# ESC_NoPilot.net
KiCad netlist of a schematic drawn in EAGLE
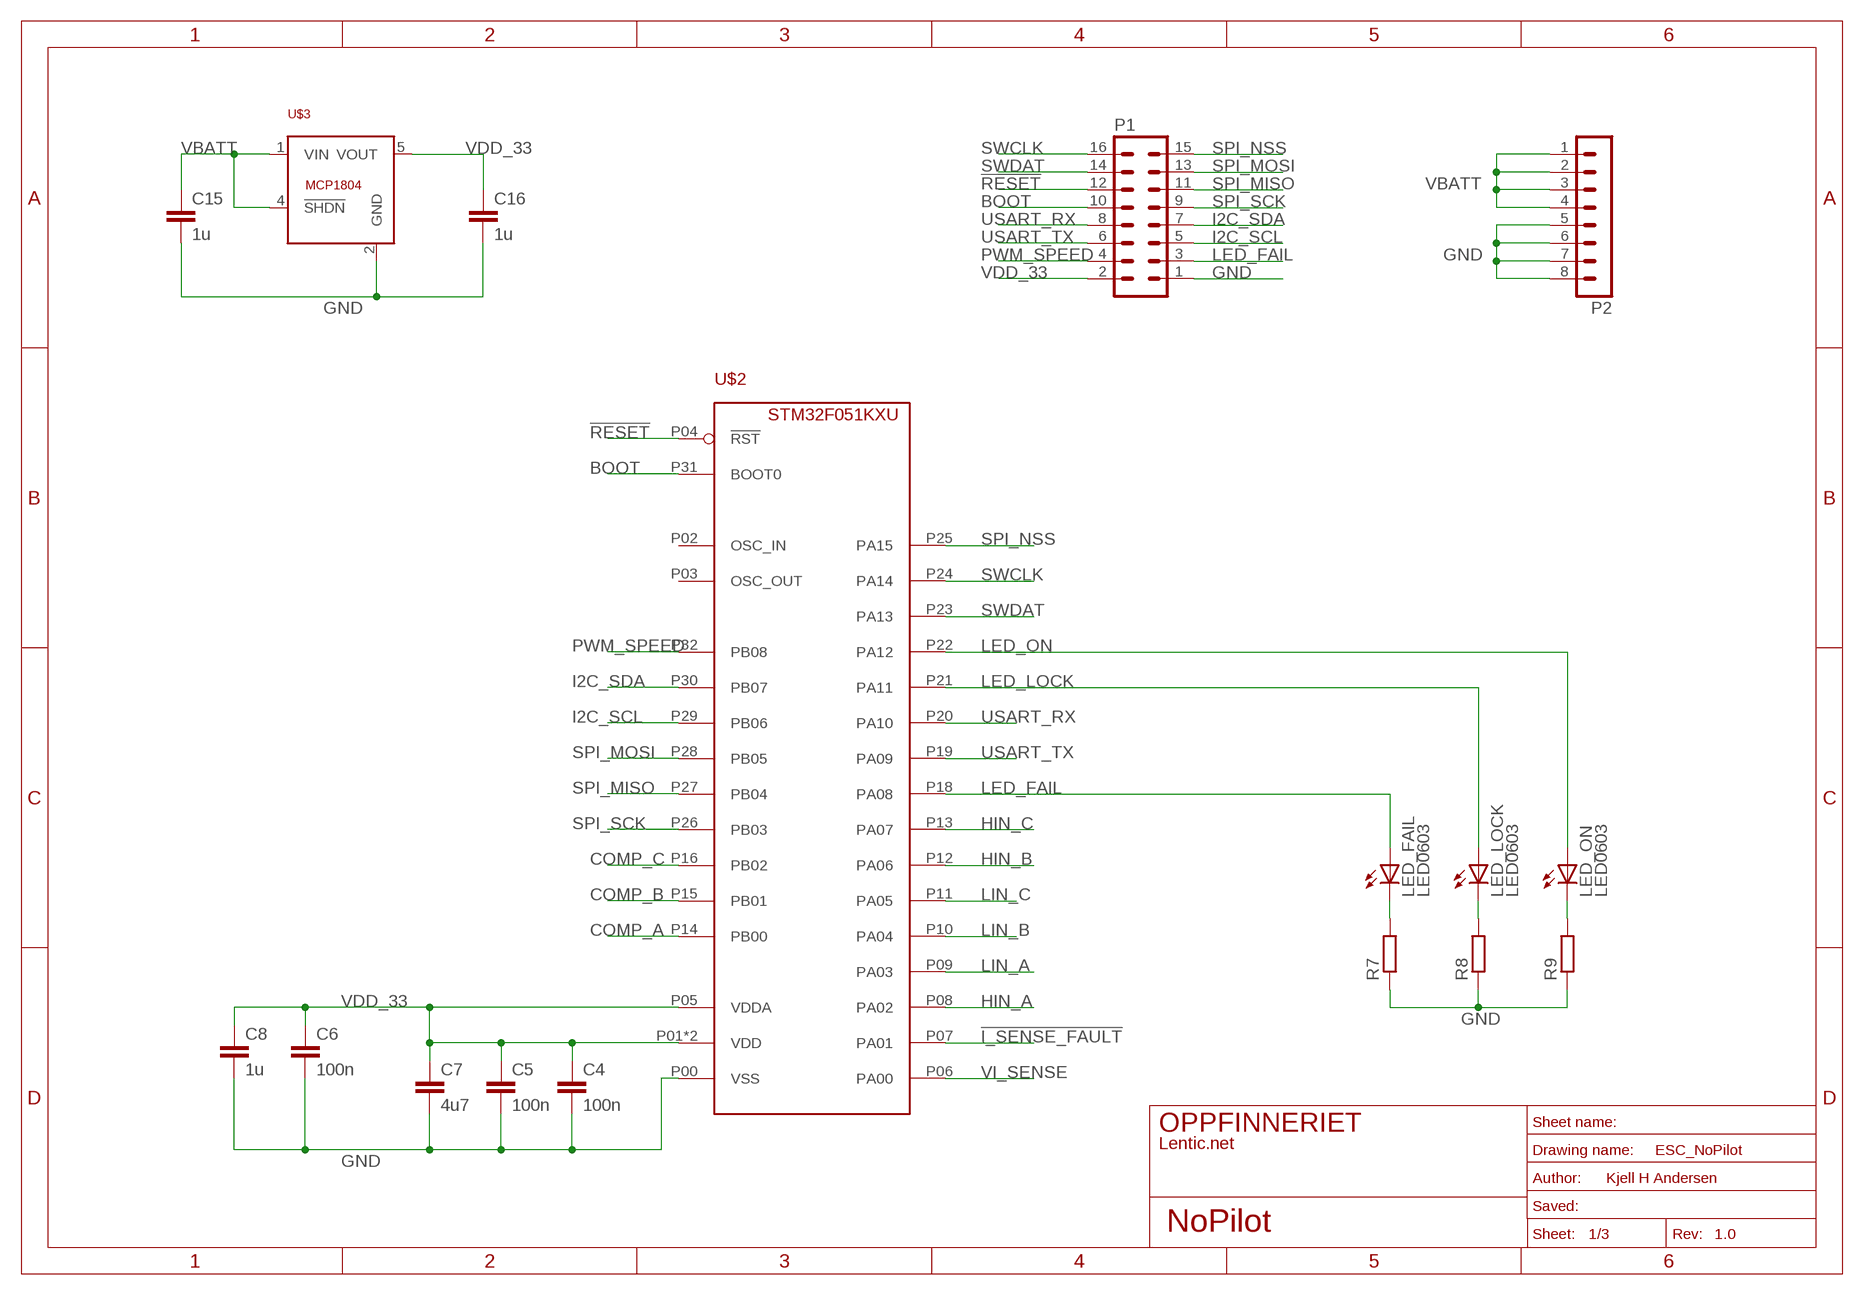
[diagram p0: schematic, sheet 1]
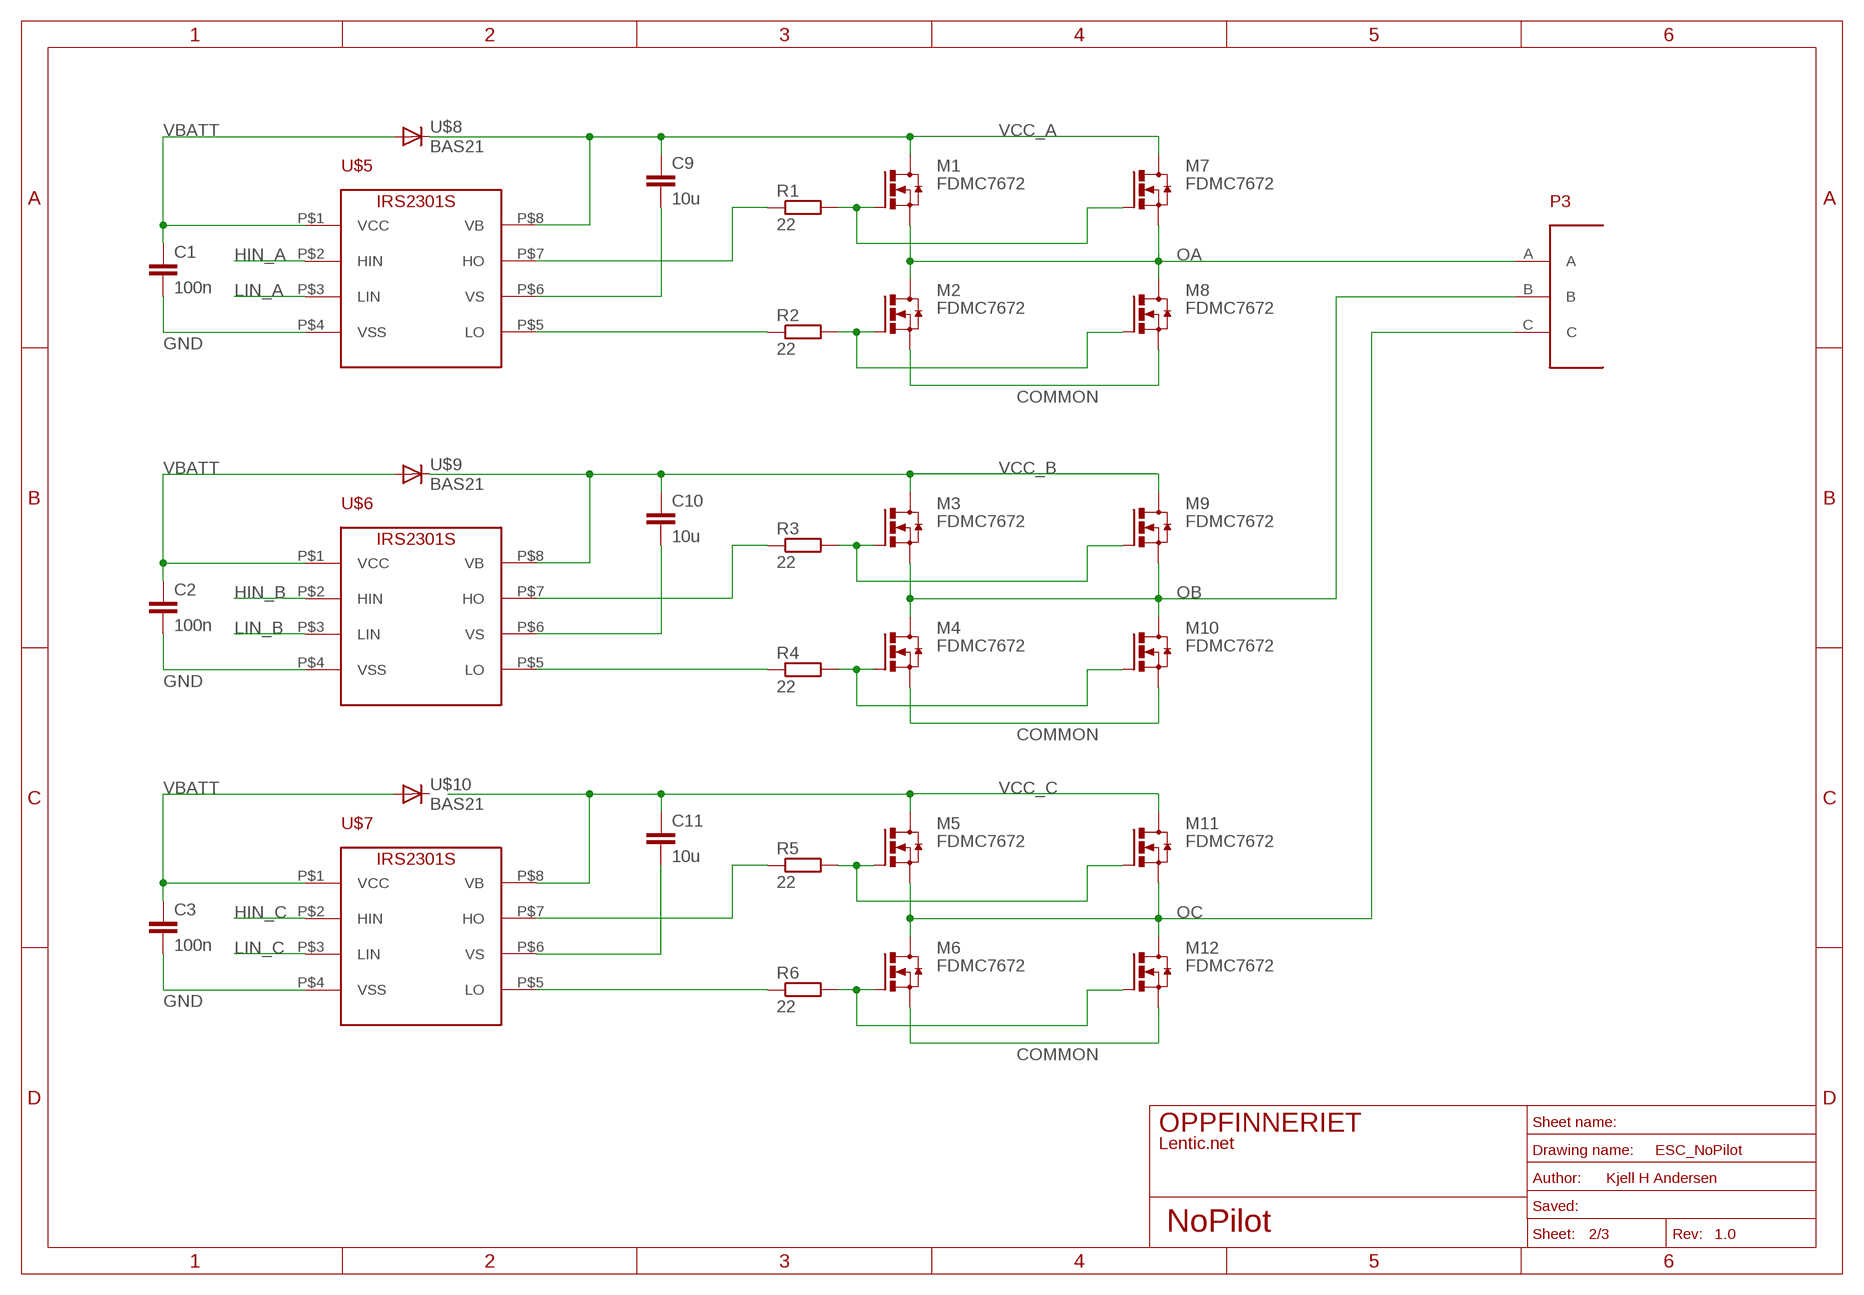
[diagram p1: schematic, sheet 2]
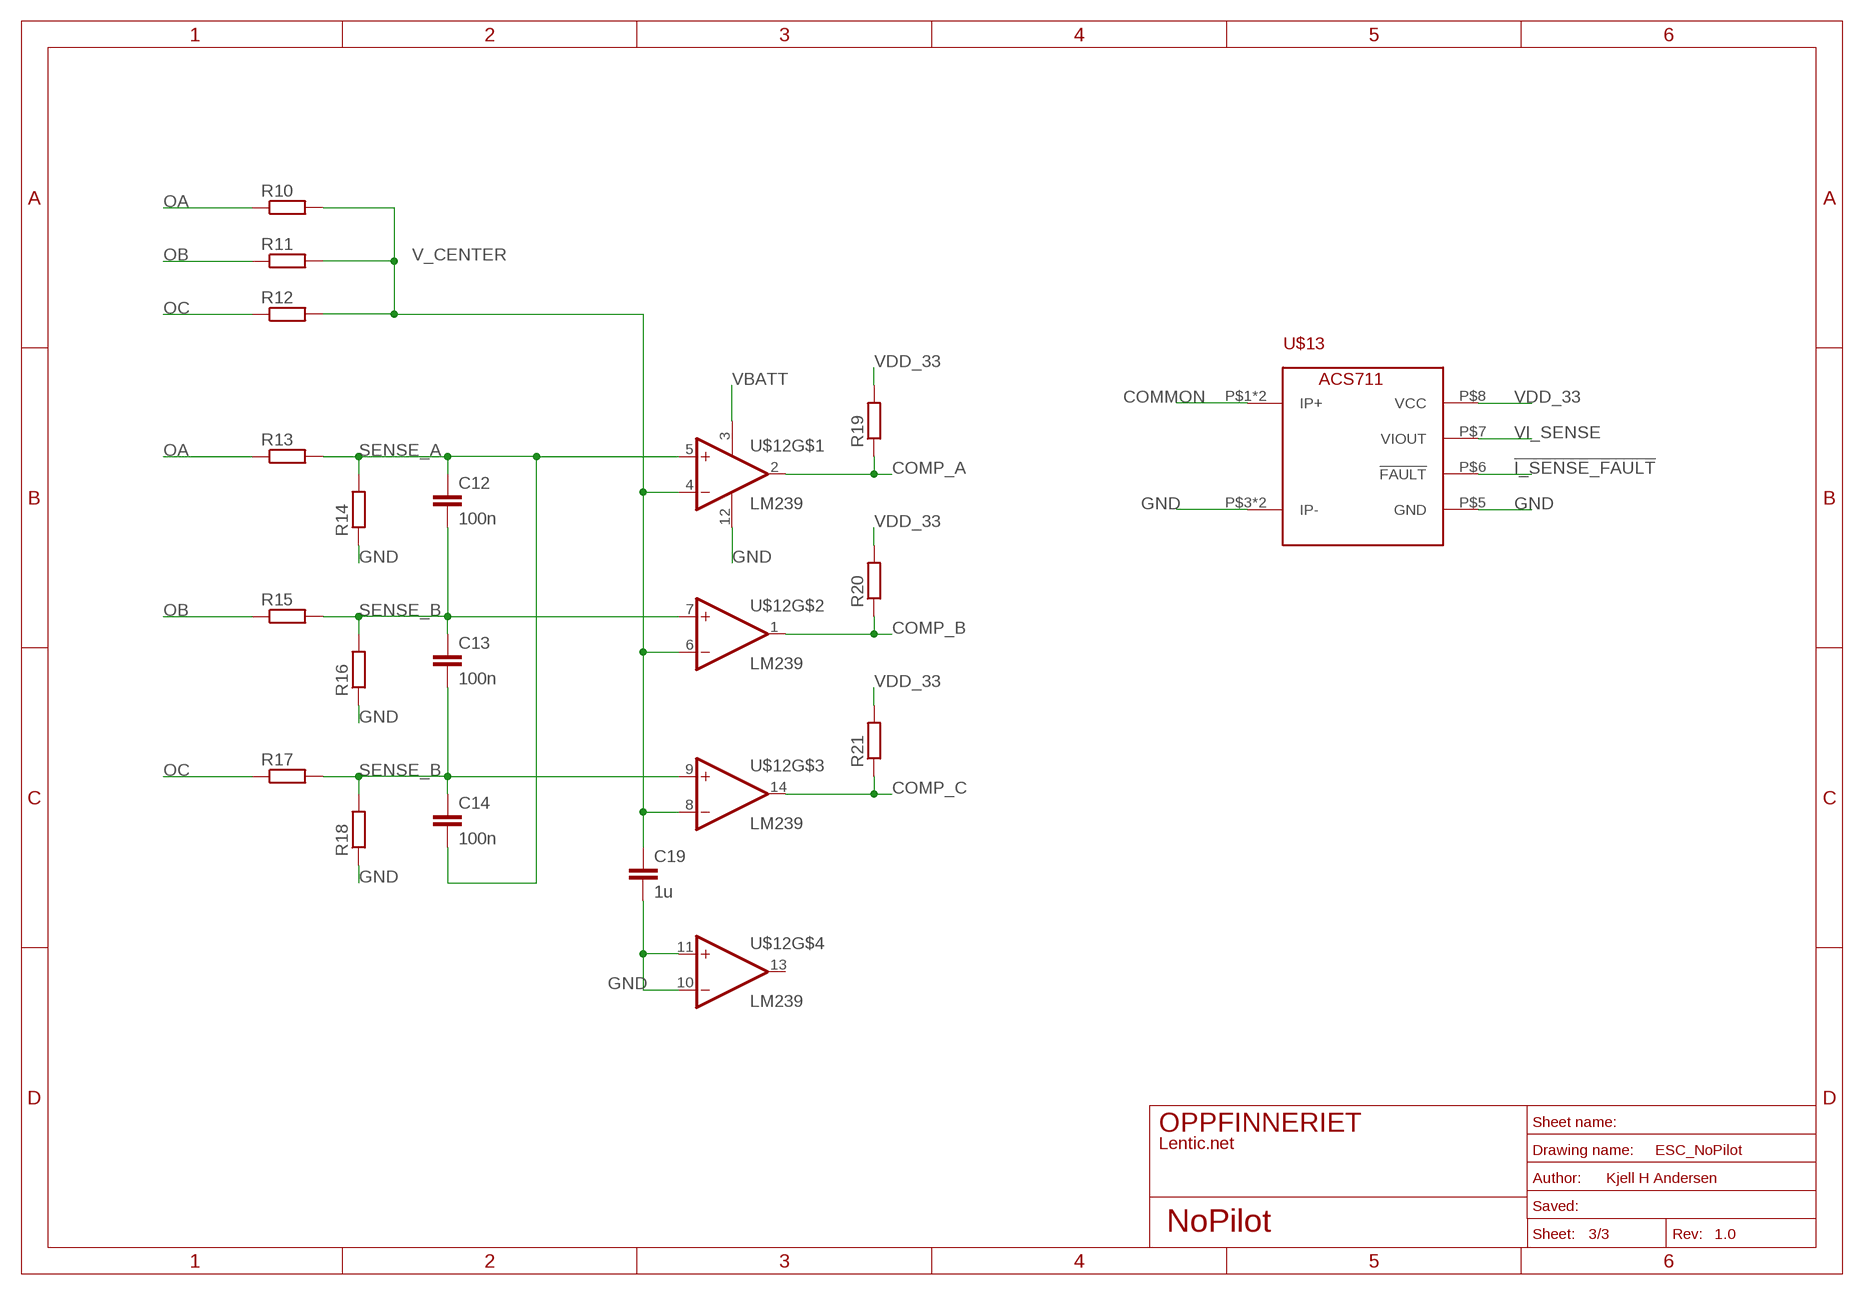
[diagram p2: schematic, sheet 3]

(export (version "E")
  (design (tool "Eeschema 10.0.6"))
  (components
    (comp (ref "C12")
      (value "100n")
      (footprint "eagle-import:C0402")
      (libsource (lib "eagle-import") (part "C-EUC0402"))
    )
    (comp (ref "C13")
      (value "100n")
      (footprint "eagle-import:C0402")
      (libsource (lib "eagle-import") (part "C-EUC0402"))
    )
    (comp (ref "C14")
      (value "100n")
      (footprint "eagle-import:C0402")
      (libsource (lib "eagle-import") (part "C-EUC0402"))
    )
    (comp (ref "C19")
      (value "1u")
      (footprint "eagle-import:C0805")
      (libsource (lib "eagle-import") (part "C-EUC0805"))
    )
    (comp (ref "R10")
      (value "R-EU_R0402")
      (footprint "eagle-import:R0402")
      (libsource (lib "eagle-import") (part "R-EU_R0402"))
    )
    (comp (ref "R11")
      (value "R-EU_R0402")
      (footprint "eagle-import:R0402")
      (libsource (lib "eagle-import") (part "R-EU_R0402"))
    )
    (comp (ref "R12")
      (value "R-EU_R0402")
      (footprint "eagle-import:R0402")
      (libsource (lib "eagle-import") (part "R-EU_R0402"))
    )
    (comp (ref "R13")
      (value "R-EU_R0402")
      (footprint "eagle-import:R0402")
      (libsource (lib "eagle-import") (part "R-EU_R0402"))
    )
    (comp (ref "R14")
      (value "R-EU_R0402")
      (footprint "eagle-import:R0402")
      (libsource (lib "eagle-import") (part "R-EU_R0402"))
    )
    (comp (ref "R15")
      (value "R-EU_R0402")
      (footprint "eagle-import:R0402")
      (libsource (lib "eagle-import") (part "R-EU_R0402"))
    )
    (comp (ref "R16")
      (value "R-EU_R0402")
      (footprint "eagle-import:R0402")
      (libsource (lib "eagle-import") (part "R-EU_R0402"))
    )
    (comp (ref "R17")
      (value "R-EU_R0402")
      (footprint "eagle-import:R0402")
      (libsource (lib "eagle-import") (part "R-EU_R0402"))
    )
    (comp (ref "R18")
      (value "R-EU_R0402")
      (footprint "eagle-import:R0402")
      (libsource (lib "eagle-import") (part "R-EU_R0402"))
    )
    (comp (ref "R19")
      (value "R-EU_R0402")
      (footprint "eagle-import:R0402")
      (libsource (lib "eagle-import") (part "R-EU_R0402"))
    )
    (comp (ref "R20")
      (value "R-EU_R0402")
      (footprint "eagle-import:R0402")
      (libsource (lib "eagle-import") (part "R-EU_R0402"))
    )
    (comp (ref "R21")
      (value "R-EU_R0402")
      (footprint "eagle-import:R0402")
      (libsource (lib "eagle-import") (part "R-EU_R0402"))
    )
    (comp (ref "U$12")
      (value "LM239")
      (footprint "eagle-import:TSSOP14")
      (libsource (lib "eagle-import") (part "LM239"))
    )
    (comp (ref "U$13")
      (value "ACS711")
      (footprint "eagle-import:SOIC8")
      (libsource (lib "eagle-import") (part "ACS711"))
    )
    (comp (ref "C4")
      (value "100n")
      (footprint "eagle-import:C0402")
      (libsource (lib "eagle-import") (part "C-EUC0402"))
    )
    (comp (ref "C5")
      (value "100n")
      (footprint "eagle-import:C0402")
      (libsource (lib "eagle-import") (part "C-EUC0402"))
    )
    (comp (ref "C6")
      (value "100n")
      (footprint "eagle-import:C0402")
      (libsource (lib "eagle-import") (part "C-EUC0402"))
    )
    (comp (ref "C7")
      (value "4u7")
      (footprint "eagle-import:C0805")
      (libsource (lib "eagle-import") (part "C-EUC0805"))
    )
    (comp (ref "C8")
      (value "1u")
      (footprint "eagle-import:C0805")
      (libsource (lib "eagle-import") (part "C-EUC0805"))
    )
    (comp (ref "C15")
      (value "1u")
      (footprint "eagle-import:C0805")
      (libsource (lib "eagle-import") (part "C-EUC0805"))
    )
    (comp (ref "C16")
      (value "1u")
      (footprint "eagle-import:C0805")
      (libsource (lib "eagle-import") (part "C-EUC0805"))
    )
    (comp (ref "LED_FAIL")
      (value "LED0603")
      (footprint "eagle-import:D0603")
      (libsource (lib "eagle-import") (part "LED0603"))
    )
    (comp (ref "LED_LOCK")
      (value "LED0603")
      (footprint "eagle-import:D0603")
      (libsource (lib "eagle-import") (part "LED0603"))
    )
    (comp (ref "LED_ON")
      (value "LED0603")
      (footprint "eagle-import:D0603")
      (libsource (lib "eagle-import") (part "LED0603"))
    )
    (comp (ref "P1")
      (value "MA08-2")
      (footprint "eagle-import:MA08-2")
      (libsource (lib "eagle-import") (part "MA08-2"))
    )
    (comp (ref "P2")
      (value "MA08-1")
      (footprint "eagle-import:MA08-1")
      (libsource (lib "eagle-import") (part "MA08-1"))
    )
    (comp (ref "R7")
      (value "R-EU_R0402")
      (footprint "eagle-import:R0402")
      (libsource (lib "eagle-import") (part "R-EU_R0402"))
    )
    (comp (ref "R8")
      (value "R-EU_R0402")
      (footprint "eagle-import:R0402")
      (libsource (lib "eagle-import") (part "R-EU_R0402"))
    )
    (comp (ref "R9")
      (value "R-EU_R0402")
      (footprint "eagle-import:R0402")
      (libsource (lib "eagle-import") (part "R-EU_R0402"))
    )
    (comp (ref "U$2")
      (value "STM32F051KXU")
      (footprint "eagle-import:UFQFPN32")
      (libsource (lib "eagle-import") (part "STM32F051KXU"))
    )
    (comp (ref "U$3")
      (value "MCP1804")
      (footprint "eagle-import:SOT23")
      (libsource (lib "eagle-import") (part "MCP1804"))
    )
    (comp (ref "C1")
      (value "100n")
      (footprint "eagle-import:C0402")
      (libsource (lib "eagle-import") (part "C-EUC0402"))
    )
    (comp (ref "C2")
      (value "100n")
      (footprint "eagle-import:C0402")
      (libsource (lib "eagle-import") (part "C-EUC0402"))
    )
    (comp (ref "C3")
      (value "100n")
      (footprint "eagle-import:C0402")
      (libsource (lib "eagle-import") (part "C-EUC0402"))
    )
    (comp (ref "C9")
      (value "10u")
      (footprint "eagle-import:C0805")
      (libsource (lib "eagle-import") (part "C-EUC0805"))
    )
    (comp (ref "C10")
      (value "10u")
      (footprint "eagle-import:C0805")
      (libsource (lib "eagle-import") (part "C-EUC0805"))
    )
    (comp (ref "C11")
      (value "10u")
      (footprint "eagle-import:C0805")
      (libsource (lib "eagle-import") (part "C-EUC0805"))
    )
    (comp (ref "M1")
      (value "FDMC7672")
      (footprint "eagle-import:MLP_3P3X3P3")
      (libsource (lib "eagle-import") (part "FDMC7672"))
    )
    (comp (ref "M2")
      (value "FDMC7672")
      (footprint "eagle-import:MLP_3P3X3P3")
      (libsource (lib "eagle-import") (part "FDMC7672"))
    )
    (comp (ref "M3")
      (value "FDMC7672")
      (footprint "eagle-import:MLP_3P3X3P3")
      (libsource (lib "eagle-import") (part "FDMC7672"))
    )
    (comp (ref "M4")
      (value "FDMC7672")
      (footprint "eagle-import:MLP_3P3X3P3")
      (libsource (lib "eagle-import") (part "FDMC7672"))
    )
    (comp (ref "M5")
      (value "FDMC7672")
      (footprint "eagle-import:MLP_3P3X3P3")
      (libsource (lib "eagle-import") (part "FDMC7672"))
    )
    (comp (ref "M6")
      (value "FDMC7672")
      (footprint "eagle-import:MLP_3P3X3P3")
      (libsource (lib "eagle-import") (part "FDMC7672"))
    )
    (comp (ref "M7")
      (value "FDMC7672")
      (footprint "eagle-import:MLP_3P3X3P3")
      (libsource (lib "eagle-import") (part "FDMC7672"))
    )
    (comp (ref "M8")
      (value "FDMC7672")
      (footprint "eagle-import:MLP_3P3X3P3")
      (libsource (lib "eagle-import") (part "FDMC7672"))
    )
    (comp (ref "M9")
      (value "FDMC7672")
      (footprint "eagle-import:MLP_3P3X3P3")
      (libsource (lib "eagle-import") (part "FDMC7672"))
    )
    (comp (ref "M10")
      (value "FDMC7672")
      (footprint "eagle-import:MLP_3P3X3P3")
      (libsource (lib "eagle-import") (part "FDMC7672"))
    )
    (comp (ref "M11")
      (value "FDMC7672")
      (footprint "eagle-import:MLP_3P3X3P3")
      (libsource (lib "eagle-import") (part "FDMC7672"))
    )
    (comp (ref "M12")
      (value "FDMC7672")
      (footprint "eagle-import:MLP_3P3X3P3")
      (libsource (lib "eagle-import") (part "FDMC7672"))
    )
    (comp (ref "P3")
      (value "3PH_SJ")
      (footprint "eagle-import:3PH_SJ")
      (libsource (lib "eagle-import") (part "3PH_SJ"))
    )
    (comp (ref "R1")
      (value "22")
      (footprint "eagle-import:R0402")
      (libsource (lib "eagle-import") (part "R-EU_R0402"))
    )
    (comp (ref "R2")
      (value "22")
      (footprint "eagle-import:R0402")
      (libsource (lib "eagle-import") (part "R-EU_R0402"))
    )
    (comp (ref "R3")
      (value "22")
      (footprint "eagle-import:R0402")
      (libsource (lib "eagle-import") (part "R-EU_R0402"))
    )
    (comp (ref "R4")
      (value "22")
      (footprint "eagle-import:R0402")
      (libsource (lib "eagle-import") (part "R-EU_R0402"))
    )
    (comp (ref "R5")
      (value "22")
      (footprint "eagle-import:R0402")
      (libsource (lib "eagle-import") (part "R-EU_R0402"))
    )
    (comp (ref "R6")
      (value "22")
      (footprint "eagle-import:R0402")
      (libsource (lib "eagle-import") (part "R-EU_R0402"))
    )
    (comp (ref "U$5")
      (value "IRS2301S")
      (footprint "eagle-import:SOIC8")
      (libsource (lib "eagle-import") (part "IRS2301S"))
    )
    (comp (ref "U$6")
      (value "IRS2301S")
      (footprint "eagle-import:SOIC8")
      (libsource (lib "eagle-import") (part "IRS2301S"))
    )
    (comp (ref "U$7")
      (value "IRS2301S")
      (footprint "eagle-import:SOIC8")
      (libsource (lib "eagle-import") (part "IRS2301S"))
    )
    (comp (ref "U$8")
      (value "BAS21")
      (footprint "eagle-import:SOT23-3")
      (libsource (lib "eagle-import") (part "BAS21"))
    )
    (comp (ref "U$9")
      (value "BAS21")
      (footprint "eagle-import:SOT23-3")
      (libsource (lib "eagle-import") (part "BAS21"))
    )
    (comp (ref "U$10")
      (value "BAS21")
      (footprint "eagle-import:SOT23-3")
      (libsource (lib "eagle-import") (part "BAS21"))
    )
  )
  (nets
    (net (code "1") (name "BOOT") (class "Default")
      (node (ref "P1") (pin "10") (pinfunction "10_10") (pintype "passive"))
      (node (ref "U$2") (pin "P31") (pinfunction "BOOT0_P31") (pintype "input"))
    )
    (net (code "2") (name "COMMON") (class "Default")
      (node (ref "M10") (pin "P1") (pinfunction "S_P1") (pintype "passive"))
      (node (ref "M10") (pin "P2") (pinfunction "S_P2") (pintype "passive"))
      (node (ref "M10") (pin "P3") (pinfunction "S_P3") (pintype "passive"))
      (node (ref "M12") (pin "P1") (pinfunction "S_P1") (pintype "passive"))
      (node (ref "M12") (pin "P2") (pinfunction "S_P2") (pintype "passive"))
      (node (ref "M12") (pin "P3") (pinfunction "S_P3") (pintype "passive"))
      (node (ref "M2") (pin "P1") (pinfunction "S_P1") (pintype "passive"))
      (node (ref "M2") (pin "P2") (pinfunction "S_P2") (pintype "passive"))
      (node (ref "M2") (pin "P3") (pinfunction "S_P3") (pintype "passive"))
      (node (ref "M4") (pin "P1") (pinfunction "S_P1") (pintype "passive"))
      (node (ref "M4") (pin "P2") (pinfunction "S_P2") (pintype "passive"))
      (node (ref "M4") (pin "P3") (pinfunction "S_P3") (pintype "passive"))
      (node (ref "M6") (pin "P1") (pinfunction "S_P1") (pintype "passive"))
      (node (ref "M6") (pin "P2") (pinfunction "S_P2") (pintype "passive"))
      (node (ref "M6") (pin "P3") (pinfunction "S_P3") (pintype "passive"))
      (node (ref "M8") (pin "P1") (pinfunction "S_P1") (pintype "passive"))
      (node (ref "M8") (pin "P2") (pinfunction "S_P2") (pintype "passive"))
      (node (ref "M8") (pin "P3") (pinfunction "S_P3") (pintype "passive"))
      (node (ref "U$13") (pin "P$1") (pinfunction "IP+_P$1") (pintype "bidirectional"))
      (node (ref "U$13") (pin "P$2") (pinfunction "IP+_P$2") (pintype "bidirectional"))
    )
    (net (code "3") (name "COMP_A") (class "Default")
      (node (ref "R19") (pin "1") (pinfunction "1_1") (pintype "passive"))
      (node (ref "U$12") (pin "2") (pinfunction "OUT_2") (pintype "open_collector"))
      (node (ref "U$2") (pin "P14") (pinfunction "PB00_P14") (pintype "bidirectional"))
    )
    (net (code "4") (name "COMP_B") (class "Default")
      (node (ref "R20") (pin "1") (pinfunction "1_1") (pintype "passive"))
      (node (ref "U$12") (pin "1") (pinfunction "OUT_1") (pintype "open_collector"))
      (node (ref "U$2") (pin "P15") (pinfunction "PB01_P15") (pintype "bidirectional"))
    )
    (net (code "5") (name "COMP_C") (class "Default")
      (node (ref "R21") (pin "1") (pinfunction "1_1") (pintype "passive"))
      (node (ref "U$12") (pin "14") (pinfunction "OUT_14") (pintype "open_collector"))
      (node (ref "U$2") (pin "P16") (pinfunction "PB02_P16") (pintype "bidirectional"))
    )
    (net (code "6") (name "GND") (class "Default")
      (node (ref "C1") (pin "2") (pinfunction "2_2") (pintype "passive"))
      (node (ref "C15") (pin "2") (pinfunction "2_2") (pintype "passive"))
      (node (ref "C16") (pin "2") (pinfunction "2_2") (pintype "passive"))
      (node (ref "C19") (pin "2") (pinfunction "2_2") (pintype "passive"))
      (node (ref "C2") (pin "2") (pinfunction "2_2") (pintype "passive"))
      (node (ref "C3") (pin "2") (pinfunction "2_2") (pintype "passive"))
      (node (ref "C4") (pin "2") (pinfunction "2_2") (pintype "passive"))
      (node (ref "C5") (pin "2") (pinfunction "2_2") (pintype "passive"))
      (node (ref "C6") (pin "2") (pinfunction "2_2") (pintype "passive"))
      (node (ref "C7") (pin "2") (pinfunction "2_2") (pintype "passive"))
      (node (ref "C8") (pin "2") (pinfunction "2_2") (pintype "passive"))
      (node (ref "P1") (pin "1") (pinfunction "1_1") (pintype "passive"))
      (node (ref "P2") (pin "5") (pinfunction "5_5") (pintype "passive"))
      (node (ref "P2") (pin "6") (pinfunction "6_6") (pintype "passive"))
      (node (ref "P2") (pin "7") (pinfunction "7_7") (pintype "passive"))
      (node (ref "P2") (pin "8") (pinfunction "8_8") (pintype "passive"))
      (node (ref "R14") (pin "1") (pinfunction "1_1") (pintype "passive"))
      (node (ref "R16") (pin "1") (pinfunction "1_1") (pintype "passive"))
      (node (ref "R18") (pin "1") (pinfunction "1_1") (pintype "passive"))
      (node (ref "R7") (pin "1") (pinfunction "1_1") (pintype "passive"))
      (node (ref "R8") (pin "1") (pinfunction "1_1") (pintype "passive"))
      (node (ref "R9") (pin "1") (pinfunction "1_1") (pintype "passive"))
      (node (ref "U$12") (pin "10") (pinfunction "-IN_10") (pintype "input"))
      (node (ref "U$12") (pin "11") (pinfunction "+IN_11") (pintype "input"))
      (node (ref "U$12") (pin "12") (pinfunction "GND_12") (pintype "power_in"))
      (node (ref "U$13") (pin "P$3") (pinfunction "IP-_P$3") (pintype "bidirectional"))
      (node (ref "U$13") (pin "P$4") (pinfunction "IP-_P$4") (pintype "bidirectional"))
      (node (ref "U$13") (pin "P$5") (pinfunction "GND_P$5") (pintype "bidirectional"))
      (node (ref "U$2") (pin "P00") (pinfunction "VSS_P00") (pintype "power_in"))
      (node (ref "U$3") (pin "2") (pinfunction "GND_2") (pintype "bidirectional"))
      (node (ref "U$5") (pin "P$4") (pinfunction "VSS_P$4") (pintype "bidirectional"))
      (node (ref "U$6") (pin "P$4") (pinfunction "VSS_P$4") (pintype "bidirectional"))
      (node (ref "U$7") (pin "P$4") (pinfunction "VSS_P$4") (pintype "bidirectional"))
    )
    (net (code "7") (name "HIN_A") (class "Default")
      (node (ref "U$2") (pin "P08") (pinfunction "PA02_P08") (pintype "bidirectional"))
      (node (ref "U$5") (pin "P$2") (pinfunction "HIN_P$2") (pintype "bidirectional"))
    )
    (net (code "8") (name "HIN_B") (class "Default")
      (node (ref "U$2") (pin "P12") (pinfunction "PA06_P12") (pintype "bidirectional"))
      (node (ref "U$6") (pin "P$2") (pinfunction "HIN_P$2") (pintype "bidirectional"))
    )
    (net (code "9") (name "HIN_C") (class "Default")
      (node (ref "U$2") (pin "P13") (pinfunction "PA07_P13") (pintype "bidirectional"))
      (node (ref "U$7") (pin "P$2") (pinfunction "HIN_P$2") (pintype "bidirectional"))
    )
    (net (code "10") (name "I2C_SCL") (class "Default")
      (node (ref "P1") (pin "5") (pinfunction "5_5") (pintype "passive"))
      (node (ref "U$2") (pin "P29") (pinfunction "PB06_P29") (pintype "bidirectional"))
    )
    (net (code "11") (name "I2C_SDA") (class "Default")
      (node (ref "P1") (pin "7") (pinfunction "7_7") (pintype "passive"))
      (node (ref "U$2") (pin "P30") (pinfunction "PB07_P30") (pintype "bidirectional"))
    )
    (net (code "12") (name "LED_FAIL") (class "Default")
      (node (ref "LED_FAIL") (pin "A") (pinfunction "A_A") (pintype "passive"))
      (node (ref "P1") (pin "3") (pinfunction "3_3") (pintype "passive"))
      (node (ref "U$2") (pin "P18") (pinfunction "PA08_P18") (pintype "bidirectional"))
    )
    (net (code "13") (name "LED_LOCK") (class "Default")
      (node (ref "LED_LOCK") (pin "A") (pinfunction "A_A") (pintype "passive"))
      (node (ref "U$2") (pin "P21") (pinfunction "PA11_P21") (pintype "bidirectional"))
    )
    (net (code "14") (name "LED_ON") (class "Default")
      (node (ref "LED_ON") (pin "A") (pinfunction "A_A") (pintype "passive"))
      (node (ref "U$2") (pin "P22") (pinfunction "PA12_P22") (pintype "bidirectional"))
    )
    (net (code "15") (name "LIN_A") (class "Default")
      (node (ref "U$2") (pin "P09") (pinfunction "PA03_P09") (pintype "bidirectional"))
      (node (ref "U$5") (pin "P$3") (pinfunction "LIN_P$3") (pintype "bidirectional"))
    )
    (net (code "16") (name "LIN_B") (class "Default")
      (node (ref "U$2") (pin "P10") (pinfunction "PA04_P10") (pintype "bidirectional"))
      (node (ref "U$6") (pin "P$3") (pinfunction "LIN_P$3") (pintype "bidirectional"))
    )
    (net (code "17") (name "LIN_C") (class "Default")
      (node (ref "U$2") (pin "P11") (pinfunction "PA05_P11") (pintype "bidirectional"))
      (node (ref "U$7") (pin "P$3") (pinfunction "LIN_P$3") (pintype "bidirectional"))
    )
    (net (code "18") (name "Net-(LED_FAIL-PadC)") (class "Default")
      (node (ref "LED_FAIL") (pin "C") (pinfunction "C_C") (pintype "passive"))
      (node (ref "R7") (pin "2") (pinfunction "2_2") (pintype "passive"))
    )
    (net (code "19") (name "Net-(LED_LOCK-PadC)") (class "Default")
      (node (ref "LED_LOCK") (pin "C") (pinfunction "C_C") (pintype "passive"))
      (node (ref "R8") (pin "2") (pinfunction "2_2") (pintype "passive"))
    )
    (net (code "20") (name "Net-(LED_ON-PadC)") (class "Default")
      (node (ref "LED_ON") (pin "C") (pinfunction "C_C") (pintype "passive"))
      (node (ref "R9") (pin "2") (pinfunction "2_2") (pintype "passive"))
    )
    (net (code "21") (name "Net-(M1-G)") (class "Default")
      (node (ref "M1") (pin "P4") (pinfunction "G_P4") (pintype "passive"))
      (node (ref "M7") (pin "P4") (pinfunction "G_P4") (pintype "passive"))
      (node (ref "R1") (pin "2") (pinfunction "2_2") (pintype "passive"))
    )
    (net (code "22") (name "Net-(M2-G)") (class "Default")
      (node (ref "M2") (pin "P4") (pinfunction "G_P4") (pintype "passive"))
      (node (ref "M8") (pin "P4") (pinfunction "G_P4") (pintype "passive"))
      (node (ref "R2") (pin "2") (pinfunction "2_2") (pintype "passive"))
    )
    (net (code "23") (name "Net-(M3-G)") (class "Default")
      (node (ref "M3") (pin "P4") (pinfunction "G_P4") (pintype "passive"))
      (node (ref "M9") (pin "P4") (pinfunction "G_P4") (pintype "passive"))
      (node (ref "R3") (pin "2") (pinfunction "2_2") (pintype "passive"))
    )
    (net (code "24") (name "Net-(M10-G)") (class "Default")
      (node (ref "M10") (pin "P4") (pinfunction "G_P4") (pintype "passive"))
      (node (ref "M4") (pin "P4") (pinfunction "G_P4") (pintype "passive"))
      (node (ref "R4") (pin "2") (pinfunction "2_2") (pintype "passive"))
    )
    (net (code "25") (name "Net-(M11-G)") (class "Default")
      (node (ref "M11") (pin "P4") (pinfunction "G_P4") (pintype "passive"))
      (node (ref "M5") (pin "P4") (pinfunction "G_P4") (pintype "passive"))
      (node (ref "R5") (pin "2") (pinfunction "2_2") (pintype "passive"))
    )
    (net (code "26") (name "Net-(M12-G)") (class "Default")
      (node (ref "M12") (pin "P4") (pinfunction "G_P4") (pintype "passive"))
      (node (ref "M6") (pin "P4") (pinfunction "G_P4") (pintype "passive"))
      (node (ref "R6") (pin "2") (pinfunction "2_2") (pintype "passive"))
    )
    (net (code "27") (name "Net-(U$5-HO)") (class "Default")
      (node (ref "R1") (pin "1") (pinfunction "1_1") (pintype "passive"))
      (node (ref "U$5") (pin "P$7") (pinfunction "HO_P$7") (pintype "bidirectional"))
    )
    (net (code "28") (name "Net-(U$5-LO)") (class "Default")
      (node (ref "R2") (pin "1") (pinfunction "1_1") (pintype "passive"))
      (node (ref "U$5") (pin "P$5") (pinfunction "LO_P$5") (pintype "bidirectional"))
    )
    (net (code "29") (name "Net-(U$5-VS)") (class "Default")
      (node (ref "C9") (pin "2") (pinfunction "2_2") (pintype "passive"))
      (node (ref "U$5") (pin "P$6") (pinfunction "VS_P$6") (pintype "bidirectional"))
    )
    (net (code "30") (name "Net-(U$6-HO)") (class "Default")
      (node (ref "R3") (pin "1") (pinfunction "1_1") (pintype "passive"))
      (node (ref "U$6") (pin "P$7") (pinfunction "HO_P$7") (pintype "bidirectional"))
    )
    (net (code "31") (name "Net-(U$6-LO)") (class "Default")
      (node (ref "R4") (pin "1") (pinfunction "1_1") (pintype "passive"))
      (node (ref "U$6") (pin "P$5") (pinfunction "LO_P$5") (pintype "bidirectional"))
    )
    (net (code "32") (name "Net-(U$6-VS)") (class "Default")
      (node (ref "C10") (pin "2") (pinfunction "2_2") (pintype "passive"))
      (node (ref "U$6") (pin "P$6") (pinfunction "VS_P$6") (pintype "bidirectional"))
    )
    (net (code "33") (name "Net-(U$7-HO)") (class "Default")
      (node (ref "R5") (pin "1") (pinfunction "1_1") (pintype "passive"))
      (node (ref "U$7") (pin "P$7") (pinfunction "HO_P$7") (pintype "bidirectional"))
    )
    (net (code "34") (name "Net-(U$7-LO)") (class "Default")
      (node (ref "R6") (pin "1") (pinfunction "1_1") (pintype "passive"))
      (node (ref "U$7") (pin "P$5") (pinfunction "LO_P$5") (pintype "bidirectional"))
    )
    (net (code "35") (name "Net-(U$7-VS)") (class "Default")
      (node (ref "C11") (pin "2") (pinfunction "2_2") (pintype "passive"))
      (node (ref "U$7") (pin "P$6") (pinfunction "VS_P$6") (pintype "bidirectional"))
    )
    (net (code "36") (name "OA") (class "Default")
      (node (ref "M1") (pin "P1") (pinfunction "S_P1") (pintype "passive"))
      (node (ref "M1") (pin "P2") (pinfunction "S_P2") (pintype "passive"))
      (node (ref "M1") (pin "P3") (pinfunction "S_P3") (pintype "passive"))
      (node (ref "M2") (pin "P0") (pinfunction "D_P0") (pintype "passive"))
      (node (ref "M2") (pin "P5") (pinfunction "D_P5") (pintype "passive"))
      (node (ref "M2") (pin "P6") (pinfunction "D_P6") (pintype "passive"))
      (node (ref "M2") (pin "P7") (pinfunction "D_P7") (pintype "passive"))
      (node (ref "M2") (pin "P8") (pinfunction "D_P8") (pintype "passive"))
      (node (ref "M7") (pin "P1") (pinfunction "S_P1") (pintype "passive"))
      (node (ref "M7") (pin "P2") (pinfunction "S_P2") (pintype "passive"))
      (node (ref "M7") (pin "P3") (pinfunction "S_P3") (pintype "passive"))
      (node (ref "M8") (pin "P0") (pinfunction "D_P0") (pintype "passive"))
      (node (ref "M8") (pin "P5") (pinfunction "D_P5") (pintype "passive"))
      (node (ref "M8") (pin "P6") (pinfunction "D_P6") (pintype "passive"))
      (node (ref "M8") (pin "P7") (pinfunction "D_P7") (pintype "passive"))
      (node (ref "M8") (pin "P8") (pinfunction "D_P8") (pintype "passive"))
      (node (ref "P3") (pin "A") (pinfunction "A_A") (pintype "bidirectional"))
      (node (ref "R10") (pin "1") (pinfunction "1_1") (pintype "passive"))
      (node (ref "R13") (pin "1") (pinfunction "1_1") (pintype "passive"))
    )
    (net (code "37") (name "OB") (class "Default")
      (node (ref "M10") (pin "P0") (pinfunction "D_P0") (pintype "passive"))
      (node (ref "M10") (pin "P5") (pinfunction "D_P5") (pintype "passive"))
      (node (ref "M10") (pin "P6") (pinfunction "D_P6") (pintype "passive"))
      (node (ref "M10") (pin "P7") (pinfunction "D_P7") (pintype "passive"))
      (node (ref "M10") (pin "P8") (pinfunction "D_P8") (pintype "passive"))
      (node (ref "M3") (pin "P1") (pinfunction "S_P1") (pintype "passive"))
      (node (ref "M3") (pin "P2") (pinfunction "S_P2") (pintype "passive"))
      (node (ref "M3") (pin "P3") (pinfunction "S_P3") (pintype "passive"))
      (node (ref "M4") (pin "P0") (pinfunction "D_P0") (pintype "passive"))
      (node (ref "M4") (pin "P5") (pinfunction "D_P5") (pintype "passive"))
      (node (ref "M4") (pin "P6") (pinfunction "D_P6") (pintype "passive"))
      (node (ref "M4") (pin "P7") (pinfunction "D_P7") (pintype "passive"))
      (node (ref "M4") (pin "P8") (pinfunction "D_P8") (pintype "passive"))
      (node (ref "M9") (pin "P1") (pinfunction "S_P1") (pintype "passive"))
      (node (ref "M9") (pin "P2") (pinfunction "S_P2") (pintype "passive"))
      (node (ref "M9") (pin "P3") (pinfunction "S_P3") (pintype "passive"))
      (node (ref "P3") (pin "B") (pinfunction "B_B") (pintype "bidirectional"))
      (node (ref "R11") (pin "1") (pinfunction "1_1") (pintype "passive"))
      (node (ref "R15") (pin "1") (pinfunction "1_1") (pintype "passive"))
    )
    (net (code "38") (name "OC") (class "Default")
      (node (ref "M11") (pin "P1") (pinfunction "S_P1") (pintype "passive"))
      (node (ref "M11") (pin "P2") (pinfunction "S_P2") (pintype "passive"))
      (node (ref "M11") (pin "P3") (pinfunction "S_P3") (pintype "passive"))
      (node (ref "M12") (pin "P0") (pinfunction "D_P0") (pintype "passive"))
      (node (ref "M12") (pin "P5") (pinfunction "D_P5") (pintype "passive"))
      (node (ref "M12") (pin "P6") (pinfunction "D_P6") (pintype "passive"))
      (node (ref "M12") (pin "P7") (pinfunction "D_P7") (pintype "passive"))
      (node (ref "M12") (pin "P8") (pinfunction "D_P8") (pintype "passive"))
      (node (ref "M5") (pin "P1") (pinfunction "S_P1") (pintype "passive"))
      (node (ref "M5") (pin "P2") (pinfunction "S_P2") (pintype "passive"))
      (node (ref "M5") (pin "P3") (pinfunction "S_P3") (pintype "passive"))
      (node (ref "M6") (pin "P0") (pinfunction "D_P0") (pintype "passive"))
      (node (ref "M6") (pin "P5") (pinfunction "D_P5") (pintype "passive"))
      (node (ref "M6") (pin "P6") (pinfunction "D_P6") (pintype "passive"))
      (node (ref "M6") (pin "P7") (pinfunction "D_P7") (pintype "passive"))
      (node (ref "M6") (pin "P8") (pinfunction "D_P8") (pintype "passive"))
      (node (ref "P3") (pin "C") (pinfunction "C_C") (pintype "bidirectional"))
      (node (ref "R12") (pin "1") (pinfunction "1_1") (pintype "passive"))
      (node (ref "R17") (pin "1") (pinfunction "1_1") (pintype "passive"))
    )
    (net (code "39") (name "PWM_SPEED") (class "Default")
      (node (ref "P1") (pin "4") (pinfunction "4_4") (pintype "passive"))
      (node (ref "U$2") (pin "P32") (pinfunction "PB08_P32") (pintype "bidirectional"))
    )
    (net (code "40") (name "SENSE_A") (class "Default")
      (node (ref "C12") (pin "1") (pinfunction "1_1") (pintype "passive"))
      (node (ref "C14") (pin "2") (pinfunction "2_2") (pintype "passive"))
      (node (ref "R13") (pin "2") (pinfunction "2_2") (pintype "passive"))
      (node (ref "R14") (pin "2") (pinfunction "2_2") (pintype "passive"))
      (node (ref "U$12") (pin "5") (pinfunction "+IN_5") (pintype "input"))
    )
    (net (code "41") (name "SENSE_B") (class "Default")
      (node (ref "C12") (pin "2") (pinfunction "2_2") (pintype "passive"))
      (node (ref "C13") (pin "1") (pinfunction "1_1") (pintype "passive"))
      (node (ref "C13") (pin "2") (pinfunction "2_2") (pintype "passive"))
      (node (ref "C14") (pin "1") (pinfunction "1_1") (pintype "passive"))
      (node (ref "R15") (pin "2") (pinfunction "2_2") (pintype "passive"))
      (node (ref "R16") (pin "2") (pinfunction "2_2") (pintype "passive"))
      (node (ref "R17") (pin "2") (pinfunction "2_2") (pintype "passive"))
      (node (ref "R18") (pin "2") (pinfunction "2_2") (pintype "passive"))
      (node (ref "U$12") (pin "7") (pinfunction "+IN_7") (pintype "input"))
      (node (ref "U$12") (pin "9") (pinfunction "+IN_9") (pintype "input"))
    )
    (net (code "42") (name "SPI_MISO") (class "Default")
      (node (ref "P1") (pin "11") (pinfunction "11_11") (pintype "passive"))
      (node (ref "U$2") (pin "P27") (pinfunction "PB04_P27") (pintype "bidirectional"))
    )
    (net (code "43") (name "SPI_MOSI") (class "Default")
      (node (ref "P1") (pin "13") (pinfunction "13_13") (pintype "passive"))
      (node (ref "U$2") (pin "P28") (pinfunction "PB05_P28") (pintype "bidirectional"))
    )
    (net (code "44") (name "SPI_NSS") (class "Default")
      (node (ref "P1") (pin "15") (pinfunction "15_15") (pintype "passive"))
      (node (ref "U$2") (pin "P25") (pinfunction "PA15_P25") (pintype "bidirectional"))
    )
    (net (code "45") (name "SPI_SCK") (class "Default")
      (node (ref "P1") (pin "9") (pinfunction "9_9") (pintype "passive"))
      (node (ref "U$2") (pin "P26") (pinfunction "PB03_P26") (pintype "bidirectional"))
    )
    (net (code "46") (name "SWCLK") (class "Default")
      (node (ref "P1") (pin "16") (pinfunction "16_16") (pintype "passive"))
      (node (ref "U$2") (pin "P24") (pinfunction "PA14_P24") (pintype "bidirectional"))
    )
    (net (code "47") (name "SWDAT") (class "Default")
      (node (ref "P1") (pin "14") (pinfunction "14_14") (pintype "passive"))
      (node (ref "U$2") (pin "P23") (pinfunction "PA13_P23") (pintype "bidirectional"))
    )
    (net (code "48") (name "USART_RX") (class "Default")
      (node (ref "P1") (pin "8") (pinfunction "8_8") (pintype "passive"))
      (node (ref "U$2") (pin "P20") (pinfunction "PA10_P20") (pintype "bidirectional"))
    )
    (net (code "49") (name "USART_TX") (class "Default")
      (node (ref "P1") (pin "6") (pinfunction "6_6") (pintype "passive"))
      (node (ref "U$2") (pin "P19") (pinfunction "PA09_P19") (pintype "bidirectional"))
    )
    (net (code "50") (name "VBATT") (class "Default")
      (node (ref "C1") (pin "1") (pinfunction "1_1") (pintype "passive"))
      (node (ref "C15") (pin "1") (pinfunction "1_1") (pintype "passive"))
      (node (ref "C2") (pin "1") (pinfunction "1_1") (pintype "passive"))
      (node (ref "C3") (pin "1") (pinfunction "1_1") (pintype "passive"))
      (node (ref "P2") (pin "1") (pinfunction "1_1") (pintype "passive"))
      (node (ref "P2") (pin "2") (pinfunction "2_2") (pintype "passive"))
      (node (ref "P2") (pin "3") (pinfunction "3_3") (pintype "passive"))
      (node (ref "P2") (pin "4") (pinfunction "4_4") (pintype "passive"))
      (node (ref "U$10") (pin "P1") (pinfunction "A_P1") (pintype "passive"))
      (node (ref "U$12") (pin "3") (pinfunction "V+_3") (pintype "power_in"))
      (node (ref "U$3") (pin "1") (pinfunction "VIN_1") (pintype "bidirectional"))
      (node (ref "U$3") (pin "4") (pinfunction "~{SHDN}_4") (pintype "bidirectional"))
      (node (ref "U$5") (pin "P$1") (pinfunction "VCC_P$1") (pintype "bidirectional"))
      (node (ref "U$6") (pin "P$1") (pinfunction "VCC_P$1") (pintype "bidirectional"))
      (node (ref "U$7") (pin "P$1") (pinfunction "VCC_P$1") (pintype "bidirectional"))
      (node (ref "U$8") (pin "P1") (pinfunction "A_P1") (pintype "passive"))
      (node (ref "U$9") (pin "P1") (pinfunction "A_P1") (pintype "passive"))
    )
    (net (code "51") (name "VCC_A") (class "Default")
      (node (ref "C9") (pin "1") (pinfunction "1_1") (pintype "passive"))
      (node (ref "M1") (pin "P0") (pinfunction "D_P0") (pintype "passive"))
      (node (ref "M1") (pin "P5") (pinfunction "D_P5") (pintype "passive"))
      (node (ref "M1") (pin "P6") (pinfunction "D_P6") (pintype "passive"))
      (node (ref "M1") (pin "P7") (pinfunction "D_P7") (pintype "passive"))
      (node (ref "M1") (pin "P8") (pinfunction "D_P8") (pintype "passive"))
      (node (ref "M7") (pin "P0") (pinfunction "D_P0") (pintype "passive"))
      (node (ref "M7") (pin "P5") (pinfunction "D_P5") (pintype "passive"))
      (node (ref "M7") (pin "P6") (pinfunction "D_P6") (pintype "passive"))
      (node (ref "M7") (pin "P7") (pinfunction "D_P7") (pintype "passive"))
      (node (ref "M7") (pin "P8") (pinfunction "D_P8") (pintype "passive"))
      (node (ref "U$5") (pin "P$8") (pinfunction "VB_P$8") (pintype "bidirectional"))
      (node (ref "U$8") (pin "P3") (pinfunction "C_P3") (pintype "passive"))
    )
    (net (code "52") (name "VCC_B") (class "Default")
      (node (ref "C10") (pin "1") (pinfunction "1_1") (pintype "passive"))
      (node (ref "M3") (pin "P0") (pinfunction "D_P0") (pintype "passive"))
      (node (ref "M3") (pin "P5") (pinfunction "D_P5") (pintype "passive"))
      (node (ref "M3") (pin "P6") (pinfunction "D_P6") (pintype "passive"))
      (node (ref "M3") (pin "P7") (pinfunction "D_P7") (pintype "passive"))
      (node (ref "M3") (pin "P8") (pinfunction "D_P8") (pintype "passive"))
      (node (ref "M9") (pin "P0") (pinfunction "D_P0") (pintype "passive"))
      (node (ref "M9") (pin "P5") (pinfunction "D_P5") (pintype "passive"))
      (node (ref "M9") (pin "P6") (pinfunction "D_P6") (pintype "passive"))
      (node (ref "M9") (pin "P7") (pinfunction "D_P7") (pintype "passive"))
      (node (ref "M9") (pin "P8") (pinfunction "D_P8") (pintype "passive"))
      (node (ref "U$6") (pin "P$8") (pinfunction "VB_P$8") (pintype "bidirectional"))
      (node (ref "U$9") (pin "P3") (pinfunction "C_P3") (pintype "passive"))
    )
    (net (code "53") (name "VCC_C") (class "Default")
      (node (ref "C11") (pin "1") (pinfunction "1_1") (pintype "passive"))
      (node (ref "M11") (pin "P0") (pinfunction "D_P0") (pintype "passive"))
      (node (ref "M11") (pin "P5") (pinfunction "D_P5") (pintype "passive"))
      (node (ref "M11") (pin "P6") (pinfunction "D_P6") (pintype "passive"))
      (node (ref "M11") (pin "P7") (pinfunction "D_P7") (pintype "passive"))
      (node (ref "M11") (pin "P8") (pinfunction "D_P8") (pintype "passive"))
      (node (ref "M5") (pin "P0") (pinfunction "D_P0") (pintype "passive"))
      (node (ref "M5") (pin "P5") (pinfunction "D_P5") (pintype "passive"))
      (node (ref "M5") (pin "P6") (pinfunction "D_P6") (pintype "passive"))
      (node (ref "M5") (pin "P7") (pinfunction "D_P7") (pintype "passive"))
      (node (ref "M5") (pin "P8") (pinfunction "D_P8") (pintype "passive"))
      (node (ref "U$7") (pin "P$8") (pinfunction "VB_P$8") (pintype "bidirectional"))
    )
    (net (code "54") (name "VDD_33") (class "Default")
      (node (ref "C16") (pin "1") (pinfunction "1_1") (pintype "passive"))
      (node (ref "C4") (pin "1") (pinfunction "1_1") (pintype "passive"))
      (node (ref "C5") (pin "1") (pinfunction "1_1") (pintype "passive"))
      (node (ref "C6") (pin "1") (pinfunction "1_1") (pintype "passive"))
      (node (ref "C7") (pin "1") (pinfunction "1_1") (pintype "passive"))
      (node (ref "C8") (pin "1") (pinfunction "1_1") (pintype "passive"))
      (node (ref "P1") (pin "2") (pinfunction "2_2") (pintype "passive"))
      (node (ref "R19") (pin "2") (pinfunction "2_2") (pintype "passive"))
      (node (ref "R20") (pin "2") (pinfunction "2_2") (pintype "passive"))
      (node (ref "R21") (pin "2") (pinfunction "2_2") (pintype "passive"))
      (node (ref "U$13") (pin "P$8") (pinfunction "VCC_P$8") (pintype "bidirectional"))
      (node (ref "U$2") (pin "P01") (pinfunction "VDD_P01") (pintype "power_in"))
      (node (ref "U$2") (pin "P05") (pinfunction "VDDA_P05") (pintype "power_in"))
      (node (ref "U$2") (pin "P17") (pinfunction "VDD_P17") (pintype "power_in"))
      (node (ref "U$3") (pin "5") (pinfunction "VOUT_5") (pintype "bidirectional"))
    )
    (net (code "55") (name "VI_SENSE") (class "Default")
      (node (ref "U$13") (pin "P$7") (pinfunction "VIOUT_P$7") (pintype "bidirectional"))
      (node (ref "U$2") (pin "P06") (pinfunction "PA00_P06") (pintype "bidirectional"))
    )
    (net (code "56") (name "V_CENTER") (class "Default")
      (node (ref "C19") (pin "1") (pinfunction "1_1") (pintype "passive"))
      (node (ref "R10") (pin "2") (pinfunction "2_2") (pintype "passive"))
      (node (ref "R11") (pin "2") (pinfunction "2_2") (pintype "passive"))
      (node (ref "R12") (pin "2") (pinfunction "2_2") (pintype "passive"))
      (node (ref "U$12") (pin "4") (pinfunction "-IN_4") (pintype "input"))
      (node (ref "U$12") (pin "6") (pinfunction "-IN_6") (pintype "input"))
      (node (ref "U$12") (pin "8") (pinfunction "-IN_8") (pintype "input"))
    )
    (net (code "57") (name "unconnected-(U$2-OSC_IN-PadP02)") (class "Default")
      (node (ref "U$2") (pin "P02") (pinfunction "OSC_IN_P02") (pintype "input"))
    )
    (net (code "58") (name "unconnected-(U$2-OSC_OUT-PadP03)") (class "Default")
      (node (ref "U$2") (pin "P03") (pinfunction "OSC_OUT_P03") (pintype "input"))
    )
    (net (code "59") (name "unconnected-(U$10-C-PadP3)") (class "Default")
      (node (ref "U$10") (pin "P3") (pinfunction "C_P3") (pintype "passive"))
    )
    (net (code "60") (name "unconnected-(U$12D-OUT-Pad13)") (class "Default")
      (node (ref "U$12") (pin "13") (pinfunction "OUT_13") (pintype "open_collector"))
    )
    (net (code "61") (name "~{I_SENSE_FAULT}") (class "Default")
      (node (ref "U$13") (pin "P$6") (pinfunction "~{FAULT}_P$6") (pintype "bidirectional"))
      (node (ref "U$2") (pin "P07") (pinfunction "PA01_P07") (pintype "bidirectional"))
    )
    (net (code "62") (name "~{RESET}") (class "Default")
      (node (ref "P1") (pin "12") (pinfunction "12_12") (pintype "passive"))
      (node (ref "U$2") (pin "P04") (pinfunction "~{RST}_P04") (pintype "input"))
    )
  )
)
